# LVDS_IFC_DAC.net
KiCad netlist of a schematic drawn in Altium Designer
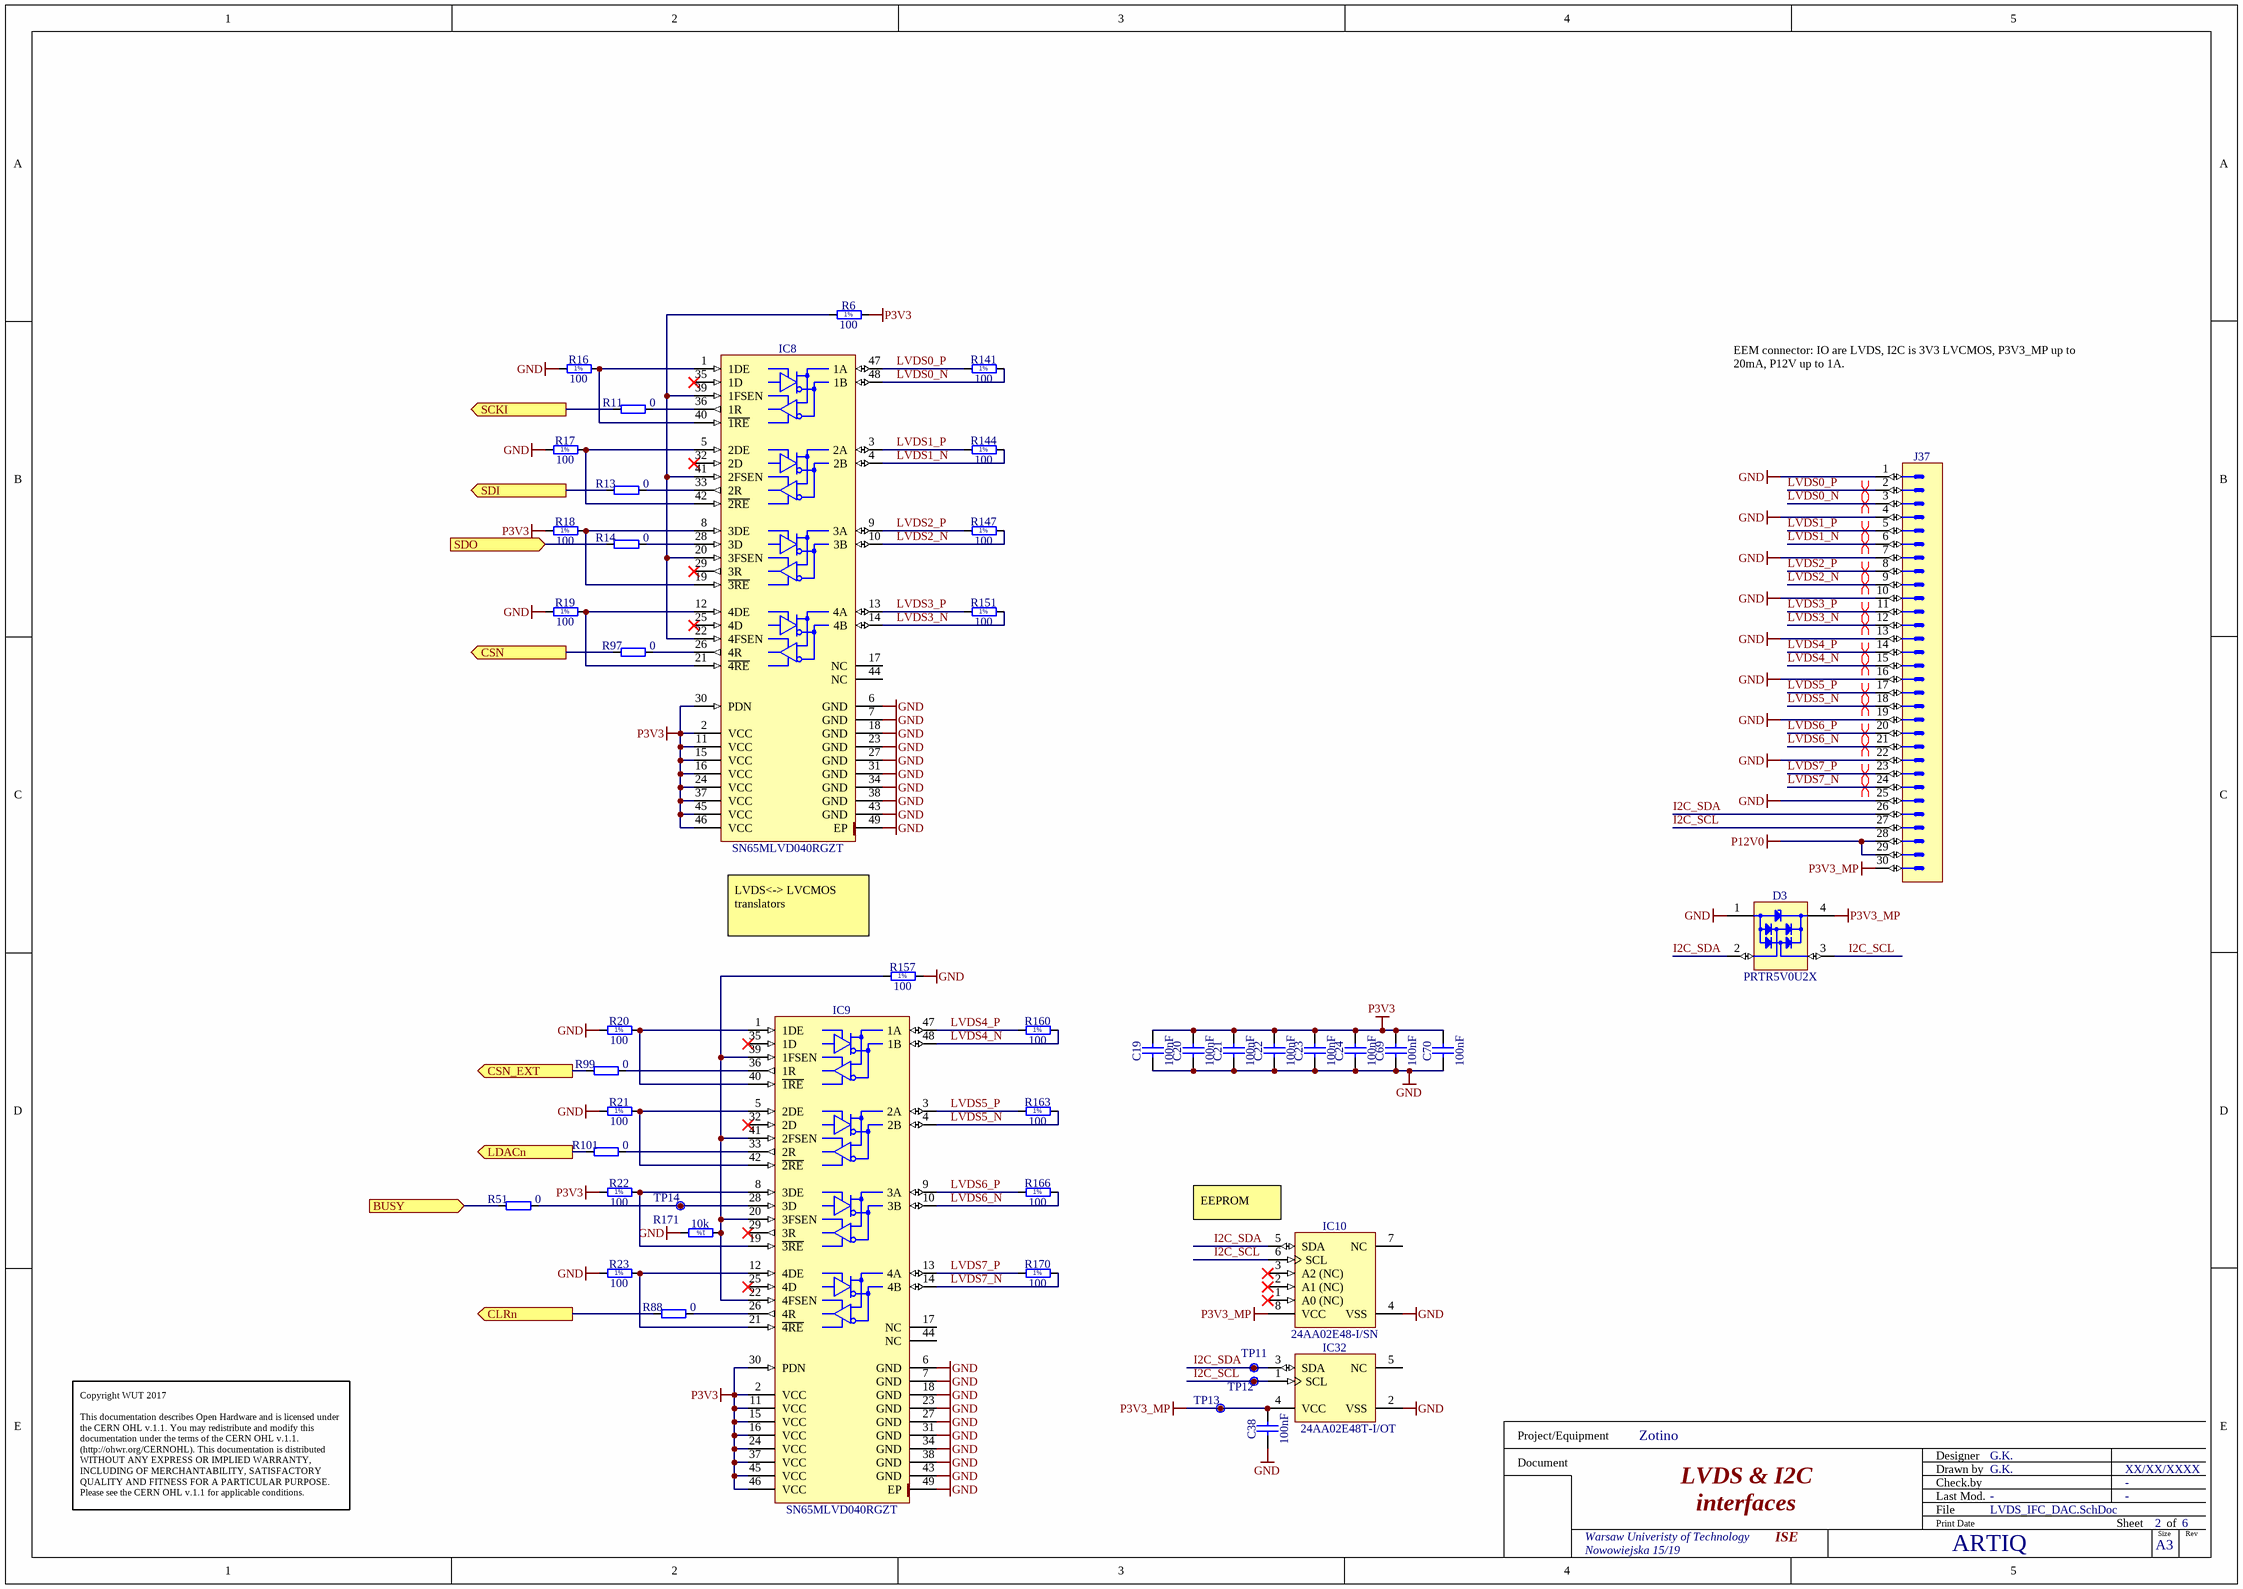
[diagram p0: LVDS_IFC_DAC.SchDoc]

(export (version "E")
  (design (tool "Eeschema 10.0.6"))
  (components
    (comp (ref "C19")
      (value "100nF")
      (footprint "CAPC1005X55N")
      (description "Non-polarised capacitor")
      (fields
        (field (name "PART NUMBER") "CC0402_100NF_16V_10%_X5R")
        (field (name "VOLTAGE") "16V")
        (field (name "AUTHOR") "CERN DEM JLC")
      )
      (libsource (lib "Capacitors") (part "Capacitor - non polarized"))
    )
    (comp (ref "C20")
      (value "100nF")
      (footprint "CAPC1005X55N")
      (description "Non-polarised capacitor")
      (fields
        (field (name "PART NUMBER") "CC0402_100NF_16V_10%_X5R")
        (field (name "VOLTAGE") "16V")
        (field (name "AUTHOR") "CERN DEM JLC")
      )
      (libsource (lib "Capacitors") (part "Capacitor - non polarized"))
    )
    (comp (ref "C21")
      (value "100nF")
      (footprint "CAPC1005X55N")
      (description "Non-polarised capacitor")
      (fields
        (field (name "PART NUMBER") "CC0402_100NF_16V_10%_X5R")
        (field (name "VOLTAGE") "16V")
        (field (name "AUTHOR") "CERN DEM JLC")
      )
      (libsource (lib "Capacitors") (part "Capacitor - non polarized"))
    )
    (comp (ref "C22")
      (value "100nF")
      (footprint "CAPC1005X55N")
      (description "Non-polarised capacitor")
      (fields
        (field (name "PART NUMBER") "CC0402_100NF_16V_10%_X5R")
        (field (name "VOLTAGE") "16V")
        (field (name "AUTHOR") "CERN DEM JLC")
      )
      (libsource (lib "Capacitors") (part "Capacitor - non polarized"))
    )
    (comp (ref "C23")
      (value "100nF")
      (footprint "CAPC1005X55N")
      (description "Non-polarised capacitor")
      (fields
        (field (name "PART NUMBER") "CC0402_100NF_16V_10%_X5R")
        (field (name "VOLTAGE") "16V")
        (field (name "AUTHOR") "CERN DEM JLC")
      )
      (libsource (lib "Capacitors") (part "Capacitor - non polarized"))
    )
    (comp (ref "C24")
      (value "100nF")
      (footprint "CAPC1005X55N")
      (description "Non-polarised capacitor")
      (fields
        (field (name "PART NUMBER") "CC0402_100NF_16V_10%_X5R")
        (field (name "VOLTAGE") "16V")
        (field (name "AUTHOR") "CERN DEM JLC")
      )
      (libsource (lib "Capacitors") (part "Capacitor - non polarized"))
    )
    (comp (ref "C38")
      (value "100nF")
      (footprint "CAPC1005X55N")
      (description "Non-polarised capacitor")
      (fields
        (field (name "PART NUMBER") "CC0402_100NF_16V_10%_X5R")
        (field (name "VOLTAGE") "16V")
        (field (name "AUTHOR") "CERN DEM JLC")
      )
      (libsource (lib "Capacitors") (part "Capacitor - non polarized"))
    )
    (comp (ref "C69")
      (value "100nF")
      (footprint "CAPC1005X55N")
      (description "Non-polarised capacitor")
      (fields
        (field (name "PART NUMBER") "CC0402_100NF_16V_10%_X5R")
        (field (name "VOLTAGE") "16V")
        (field (name "AUTHOR") "CERN DEM JLC")
      )
      (libsource (lib "Capacitors") (part "Capacitor - non polarized"))
    )
    (comp (ref "C70")
      (value "100nF")
      (footprint "CAPC1005X55N")
      (description "Non-polarised capacitor")
      (fields
        (field (name "PART NUMBER") "CC0402_100NF_16V_10%_X5R")
        (field (name "VOLTAGE") "16V")
        (field (name "AUTHOR") "CERN DEM JLC")
      )
      (libsource (lib "Capacitors") (part "Capacitor - non polarized"))
    )
    (comp (ref "D3")
      (value "PRTR5V0U2X")
      (footprint "SOT190P230X110-4N")
      (description "Ultra Low Capacitance Double Rail-to-Rail ESD Protection Diode")
      (fields
        (field (name "VOLTAGE") "5.5V")
        (field (name "MANUFACTURER") "NXP SEMICONDUCTORS")
        (field (name "AUTHOR") "CERN DEM JLC")
      )
      (libsource (lib "ICs And Semiconductors") (part "PRTR5V0U2X"))
    )
    (comp (ref "IC8")
      (value "SN65MLVD040RGZT")
      (footprint "QFN50P700X700X100-49N-S420")
      (description "4-Channel Half-Duplex M-LVDS Line Transceiver")
      (fields (field (name "MANUFACTURER") "TEXAS INSTRUMENTS") (field (name "AUTHOR") "CERN DEM JLC"))
      (libsource (lib "ICs And Semiconductors") (part "SN65MLVD040"))
    )
    (comp (ref "IC9")
      (value "SN65MLVD040RGZT")
      (footprint "QFN50P700X700X100-49N-S420")
      (description "4-Channel Half-Duplex M-LVDS Line Transceiver")
      (fields (field (name "MANUFACTURER") "TEXAS INSTRUMENTS") (field (name "AUTHOR") "CERN DEM JLC"))
      (libsource (lib "ICs And Semiconductors") (part "SN65MLVD040"))
    )
    (comp (ref "IC10")
      (value "24AA02E48-I/SN")
      (footprint "SOIC127P600X175-8N")
      (description "1.7V-5.5V, 2K I2C™ Serial EEPROMs with EUI-48™ Node Identity")
      (fields (field (name "MANUFACTURER") "MICROCHIP TECHNOLOGY") (field (name "AUTHOR") "CERN DEM MR"))
      (libsource (lib "ICS-logic") (part "MEM_24AA02E48-I/SN"))
    )
    (comp (ref "IC32")
      (value "24AA02E48T-I/OT")
      (footprint "SOT95P280X145-5N")
      (description "1.7V-5.5V, 2K I2C Serial EEPROM With EUI-48 Node Identity")
      (fields (field (name "MANUFACTURER") "MICROCHIP TECHNOLOGY") (field (name "AUTHOR") "CERN DEM MR"))
      (libsource (lib "ICs And Semiconductors") (part "24AA02E48T-I/OT"))
    )
    (comp (ref "J37")
      (value "~")
      (footprint "3M_N2530-6002RB")
      (description "Connector 30 Male")
      (fields
        (field (name "PART NUMBER") "3M_N2530-6002RB")
        (field (name "MANUFACTURER") "3M")
        (field (name "AUTHOR") "CERN DEM JLC")
      )
      (libsource (lib "Connectors") (part "Connector 30 Male"))
    )
    (comp (ref "R6")
      (value "100")
      (footprint "RESC1005X40N")
      (description "Resistor - 1%")
      (fields
        (field (name "PART NUMBER") "R0402_100R_1%_0.1W_100PPM")
        (field (name "POWER") "0.1W")
        (field (name "AUTHOR") "CERN DEM JLC")
      )
      (libsource (lib "Resistors") (part "Resistor - 1%"))
    )
    (comp (ref "R11")
      (value "0")
      (footprint "RESC1005X40N")
      (description "Resistor")
      (fields
        (field (name "PART NUMBER") "R0402_0R_JUMPER")
        (field (name "MANUFACTURER") "GENERIC")
        (field (name "AUTHOR") "CERN DEM JLC")
      )
      (libsource (lib "Resistors") (part "Resistor"))
    )
    (comp (ref "R13")
      (value "0")
      (footprint "RESC1005X40N")
      (description "Resistor")
      (fields
        (field (name "PART NUMBER") "R0402_0R_JUMPER")
        (field (name "MANUFACTURER") "GENERIC")
        (field (name "AUTHOR") "CERN DEM JLC")
      )
      (libsource (lib "Resistors") (part "Resistor"))
    )
    (comp (ref "R14")
      (value "0")
      (footprint "RESC1005X40N")
      (description "Resistor")
      (fields
        (field (name "PART NUMBER") "R0402_0R_JUMPER")
        (field (name "MANUFACTURER") "GENERIC")
        (field (name "AUTHOR") "CERN DEM JLC")
      )
      (libsource (lib "Resistors") (part "Resistor"))
    )
    (comp (ref "R16")
      (value "100")
      (footprint "RESC1005X40N")
      (description "Resistor - 1%")
      (fields
        (field (name "PART NUMBER") "R0402_100R_1%_0.1W_100PPM")
        (field (name "POWER") "0.1W")
        (field (name "AUTHOR") "CERN DEM JLC")
      )
      (libsource (lib "Resistors") (part "Resistor - 1%"))
    )
    (comp (ref "R17")
      (value "100")
      (footprint "RESC1005X40N")
      (description "Resistor - 1%")
      (fields
        (field (name "PART NUMBER") "R0402_100R_1%_0.1W_100PPM")
        (field (name "POWER") "0.1W")
        (field (name "AUTHOR") "CERN DEM JLC")
      )
      (libsource (lib "Resistors") (part "Resistor - 1%"))
    )
    (comp (ref "R18")
      (value "100")
      (footprint "RESC1005X40N")
      (description "Resistor - 1%")
      (fields
        (field (name "PART NUMBER") "R0402_100R_1%_0.1W_100PPM")
        (field (name "POWER") "0.1W")
        (field (name "AUTHOR") "CERN DEM JLC")
      )
      (libsource (lib "Resistors") (part "Resistor - 1%"))
    )
    (comp (ref "R19")
      (value "100")
      (footprint "RESC1005X40N")
      (description "Resistor - 1%")
      (fields
        (field (name "PART NUMBER") "R0402_100R_1%_0.1W_100PPM")
        (field (name "POWER") "0.1W")
        (field (name "AUTHOR") "CERN DEM JLC")
      )
      (libsource (lib "Resistors") (part "Resistor - 1%"))
    )
    (comp (ref "R20")
      (value "100")
      (footprint "RESC1005X40N")
      (description "Resistor - 1%")
      (fields
        (field (name "PART NUMBER") "R0402_100R_1%_0.1W_100PPM")
        (field (name "POWER") "0.1W")
        (field (name "AUTHOR") "CERN DEM JLC")
      )
      (libsource (lib "Resistors") (part "Resistor - 1%"))
    )
    (comp (ref "R21")
      (value "100")
      (footprint "RESC1005X40N")
      (description "Resistor - 1%")
      (fields
        (field (name "PART NUMBER") "R0402_100R_1%_0.1W_100PPM")
        (field (name "POWER") "0.1W")
        (field (name "AUTHOR") "CERN DEM JLC")
      )
      (libsource (lib "Resistors") (part "Resistor - 1%"))
    )
    (comp (ref "R22")
      (value "100")
      (footprint "RESC1005X40N")
      (description "Resistor - 1%")
      (fields
        (field (name "PART NUMBER") "R0402_100R_1%_0.1W_100PPM")
        (field (name "POWER") "0.1W")
        (field (name "AUTHOR") "CERN DEM JLC")
      )
      (libsource (lib "Resistors") (part "Resistor - 1%"))
    )
    (comp (ref "R23")
      (value "100")
      (footprint "RESC1005X40N")
      (description "Resistor - 1%")
      (fields
        (field (name "PART NUMBER") "R0402_100R_1%_0.1W_100PPM")
        (field (name "POWER") "0.1W")
        (field (name "AUTHOR") "CERN DEM JLC")
      )
      (libsource (lib "Resistors") (part "Resistor - 1%"))
    )
    (comp (ref "R51")
      (value "0")
      (footprint "RESC1005X40N")
      (description "Resistor")
      (fields
        (field (name "PART NUMBER") "R0402_0R_JUMPER")
        (field (name "MANUFACTURER") "GENERIC")
        (field (name "AUTHOR") "CERN DEM JLC")
      )
      (libsource (lib "Resistors") (part "Resistor"))
    )
    (comp (ref "R88")
      (value "0")
      (footprint "RESC1005X40N")
      (description "Resistor")
      (fields
        (field (name "PART NUMBER") "R0402_0R_JUMPER")
        (field (name "MANUFACTURER") "GENERIC")
        (field (name "AUTHOR") "CERN DEM JLC")
      )
      (libsource (lib "Resistors") (part "Resistor"))
    )
    (comp (ref "R97")
      (value "0")
      (footprint "RESC1005X40N")
      (description "Resistor")
      (fields
        (field (name "PART NUMBER") "R0402_0R_JUMPER")
        (field (name "MANUFACTURER") "GENERIC")
        (field (name "AUTHOR") "CERN DEM JLC")
      )
      (libsource (lib "Resistors") (part "Resistor"))
    )
    (comp (ref "R99")
      (value "0")
      (footprint "RESC1005X40N")
      (description "Resistor")
      (fields
        (field (name "PART NUMBER") "R0402_0R_JUMPER")
        (field (name "MANUFACTURER") "GENERIC")
        (field (name "AUTHOR") "CERN DEM JLC")
      )
      (libsource (lib "Resistors") (part "Resistor"))
    )
    (comp (ref "R101")
      (value "0")
      (footprint "RESC1005X40N")
      (description "Resistor")
      (fields
        (field (name "PART NUMBER") "R0402_0R_JUMPER")
        (field (name "MANUFACTURER") "GENERIC")
        (field (name "AUTHOR") "CERN DEM JLC")
      )
      (libsource (lib "Resistors") (part "Resistor"))
    )
    (comp (ref "R141")
      (value "100")
      (footprint "RESC1005X40N")
      (description "Resistor - 1%")
      (fields
        (field (name "PART NUMBER") "R0402_100R_1%_0.1W_100PPM")
        (field (name "POWER") "0.1W")
        (field (name "AUTHOR") "CERN DEM JLC")
      )
      (libsource (lib "Resistors") (part "Resistor - 1%"))
    )
    (comp (ref "R144")
      (value "100")
      (footprint "RESC1005X40N")
      (description "Resistor - 1%")
      (fields
        (field (name "PART NUMBER") "R0402_100R_1%_0.1W_100PPM")
        (field (name "POWER") "0.1W")
        (field (name "AUTHOR") "CERN DEM JLC")
      )
      (libsource (lib "Resistors") (part "Resistor - 1%"))
    )
    (comp (ref "R147")
      (value "100")
      (footprint "RESC1005X40N")
      (description "Resistor - 1%")
      (fields
        (field (name "PART NUMBER") "R0402_100R_1%_0.1W_100PPM")
        (field (name "POWER") "0.1W")
        (field (name "AUTHOR") "CERN DEM JLC")
      )
      (libsource (lib "Resistors") (part "Resistor - 1%"))
    )
    (comp (ref "R151")
      (value "100")
      (footprint "RESC1005X40N")
      (description "Resistor - 1%")
      (fields
        (field (name "PART NUMBER") "R0402_100R_1%_0.1W_100PPM")
        (field (name "POWER") "0.1W")
        (field (name "AUTHOR") "CERN DEM JLC")
      )
      (libsource (lib "Resistors") (part "Resistor - 1%"))
    )
    (comp (ref "R157")
      (value "100")
      (footprint "RESC1005X40N")
      (description "Resistor - 1%")
      (fields
        (field (name "PART NUMBER") "R0402_100R_1%_0.1W_100PPM")
        (field (name "POWER") "0.1W")
        (field (name "AUTHOR") "CERN DEM JLC")
      )
      (libsource (lib "Resistors") (part "Resistor - 1%"))
    )
    (comp (ref "R160")
      (value "100")
      (footprint "RESC1005X40N")
      (description "Resistor - 1%")
      (fields
        (field (name "PART NUMBER") "R0402_100R_1%_0.1W_100PPM")
        (field (name "POWER") "0.1W")
        (field (name "AUTHOR") "CERN DEM JLC")
      )
      (libsource (lib "Resistors") (part "Resistor - 1%"))
    )
    (comp (ref "R163")
      (value "100")
      (footprint "RESC1005X40N")
      (description "Resistor - 1%")
      (fields
        (field (name "PART NUMBER") "R0402_100R_1%_0.1W_100PPM")
        (field (name "POWER") "0.1W")
        (field (name "AUTHOR") "CERN DEM JLC")
      )
      (libsource (lib "Resistors") (part "Resistor - 1%"))
    )
    (comp (ref "R166")
      (value "100")
      (footprint "RESC1005X40N")
      (description "Resistor - 1%")
      (fields
        (field (name "PART NUMBER") "R0402_100R_1%_0.1W_100PPM")
        (field (name "POWER") "0.1W")
        (field (name "AUTHOR") "CERN DEM JLC")
      )
      (libsource (lib "Resistors") (part "Resistor - 1%"))
    )
    (comp (ref "R170")
      (value "100")
      (footprint "RESC1005X40N")
      (description "Resistor - 1%")
      (fields
        (field (name "PART NUMBER") "R0402_100R_1%_0.1W_100PPM")
        (field (name "POWER") "0.1W")
        (field (name "AUTHOR") "CERN DEM JLC")
      )
      (libsource (lib "Resistors") (part "Resistor - 1%"))
    )
    (comp (ref "R171")
      (value "10k")
      (footprint "RESC1005X40N")
      (description "Resistor - 1%")
      (fields
        (field (name "PART NUMBER") "R0402_10K_1%_0.0625W_100PPM")
        (field (name "POWER") "0.0625W")
        (field (name "AUTHOR") "CERN DEM JLC")
      )
      (libsource (lib "Resistors") (part "Resistor - 1%"))
    )
    (comp (ref "TP11")
      (value "Test Point")
      (footprint "TPS127")
      (fields (field (name "PART NUMBER") "SMD_PAD_1.27X1.27MM") (field (name "AUTHOR") "CERN DEM JLC"))
      (libsource (lib "Eletro-mechanical") (part "Test Point"))
    )
    (comp (ref "TP12")
      (value "Test Point")
      (footprint "TPS127")
      (fields (field (name "PART NUMBER") "SMD_PAD_1.27X1.27MM") (field (name "AUTHOR") "CERN DEM JLC"))
      (libsource (lib "Eletro-mechanical") (part "Test Point"))
    )
    (comp (ref "TP13")
      (value "Test Point")
      (footprint "TPS127")
      (fields (field (name "PART NUMBER") "SMD_PAD_1.27X1.27MM") (field (name "AUTHOR") "CERN DEM JLC"))
      (libsource (lib "Eletro-mechanical") (part "Test Point"))
    )
    (comp (ref "TP14")
      (value "Test Point")
      (footprint "TPS127")
      (fields (field (name "PART NUMBER") "SMD_PAD_1.27X1.27MM") (field (name "AUTHOR") "CERN DEM JLC"))
      (libsource (lib "Eletro-mechanical") (part "Test Point"))
    )
  )
  (nets
    (net (code "1") (name "/BUSY") (class "Default")
      (node (ref "R51") (pin "1") (pinfunction "1_1") (pintype "passive"))
    )
    (net (code "2") (name "/CLRn") (class "Default")
      (node (ref "R88") (pin "1") (pinfunction "1_1") (pintype "passive"))
    )
    (net (code "3") (name "/CSN") (class "Default")
      (node (ref "R97") (pin "1") (pinfunction "1_1") (pintype "passive"))
    )
    (net (code "4") (name "/CSN_EXT") (class "Default")
      (node (ref "R99") (pin "1") (pinfunction "1_1") (pintype "passive"))
    )
    (net (code "5") (name "/I2C_SCL") (class "Default")
      (node (ref "D3") (pin "3") (pinfunction "I/O2_3") (pintype "bidirectional"))
      (node (ref "IC10") (pin "6") (pinfunction "SCL_6") (pintype "input"))
      (node (ref "IC32") (pin "1") (pinfunction "SCL_1") (pintype "input"))
      (node (ref "J37") (pin "27") (pinfunction "27_27") (pintype "bidirectional"))
      (node (ref "TP12") (pin "1") (pinfunction "1_1") (pintype "bidirectional"))
    )
    (net (code "6") (name "/I2C_SDA") (class "Default")
      (node (ref "D3") (pin "2") (pinfunction "I/O1_2") (pintype "bidirectional"))
      (node (ref "IC10") (pin "5") (pinfunction "SDA_5") (pintype "bidirectional"))
      (node (ref "IC32") (pin "3") (pinfunction "SDA_3") (pintype "bidirectional"))
      (node (ref "J37") (pin "26") (pinfunction "26_26") (pintype "bidirectional"))
      (node (ref "TP11") (pin "1") (pinfunction "1_1") (pintype "bidirectional"))
    )
    (net (code "7") (name "/LDACn") (class "Default")
      (node (ref "R101") (pin "1") (pinfunction "1_1") (pintype "passive"))
    )
    (net (code "8") (name "/LVDS0_N") (class "Default")
      (node (ref "IC8") (pin "48") (pinfunction "1B_48") (pintype "bidirectional"))
      (node (ref "J37") (pin "3") (pinfunction "3_3") (pintype "bidirectional"))
      (node (ref "R141") (pin "2") (pinfunction "2_2") (pintype "passive"))
    )
    (net (code "9") (name "/LVDS0_P") (class "Default")
      (node (ref "IC8") (pin "47") (pinfunction "1A_47") (pintype "bidirectional"))
      (node (ref "J37") (pin "2") (pinfunction "2_2") (pintype "bidirectional"))
      (node (ref "R141") (pin "1") (pinfunction "1_1") (pintype "passive"))
    )
    (net (code "10") (name "/LVDS1_N") (class "Default")
      (node (ref "IC8") (pin "4") (pinfunction "2B_4") (pintype "bidirectional"))
      (node (ref "J37") (pin "6") (pinfunction "6_6") (pintype "bidirectional"))
      (node (ref "R144") (pin "2") (pinfunction "2_2") (pintype "passive"))
    )
    (net (code "11") (name "/LVDS1_P") (class "Default")
      (node (ref "IC8") (pin "3") (pinfunction "2A_3") (pintype "bidirectional"))
      (node (ref "J37") (pin "5") (pinfunction "5_5") (pintype "bidirectional"))
      (node (ref "R144") (pin "1") (pinfunction "1_1") (pintype "passive"))
    )
    (net (code "12") (name "/LVDS2_N") (class "Default")
      (node (ref "IC8") (pin "10") (pinfunction "3B_10") (pintype "bidirectional"))
      (node (ref "J37") (pin "9") (pinfunction "9_9") (pintype "bidirectional"))
      (node (ref "R147") (pin "2") (pinfunction "2_2") (pintype "passive"))
    )
    (net (code "13") (name "/LVDS2_P") (class "Default")
      (node (ref "IC8") (pin "9") (pinfunction "3A_9") (pintype "bidirectional"))
      (node (ref "J37") (pin "8") (pinfunction "8_8") (pintype "bidirectional"))
      (node (ref "R147") (pin "1") (pinfunction "1_1") (pintype "passive"))
    )
    (net (code "14") (name "/LVDS3_N") (class "Default")
      (node (ref "IC8") (pin "14") (pinfunction "4B_14") (pintype "bidirectional"))
      (node (ref "J37") (pin "12") (pinfunction "12_12") (pintype "bidirectional"))
      (node (ref "R151") (pin "2") (pinfunction "2_2") (pintype "passive"))
    )
    (net (code "15") (name "/LVDS3_P") (class "Default")
      (node (ref "IC8") (pin "13") (pinfunction "4A_13") (pintype "bidirectional"))
      (node (ref "J37") (pin "11") (pinfunction "11_11") (pintype "bidirectional"))
      (node (ref "R151") (pin "1") (pinfunction "1_1") (pintype "passive"))
    )
    (net (code "16") (name "/LVDS4_N") (class "Default")
      (node (ref "IC9") (pin "48") (pinfunction "1B_48") (pintype "bidirectional"))
      (node (ref "J37") (pin "15") (pinfunction "15_15") (pintype "bidirectional"))
      (node (ref "R160") (pin "2") (pinfunction "2_2") (pintype "passive"))
    )
    (net (code "17") (name "/LVDS4_P") (class "Default")
      (node (ref "IC9") (pin "47") (pinfunction "1A_47") (pintype "bidirectional"))
      (node (ref "J37") (pin "14") (pinfunction "14_14") (pintype "bidirectional"))
      (node (ref "R160") (pin "1") (pinfunction "1_1") (pintype "passive"))
    )
    (net (code "18") (name "/LVDS5_N") (class "Default")
      (node (ref "IC9") (pin "4") (pinfunction "2B_4") (pintype "bidirectional"))
      (node (ref "J37") (pin "18") (pinfunction "18_18") (pintype "bidirectional"))
      (node (ref "R163") (pin "2") (pinfunction "2_2") (pintype "passive"))
    )
    (net (code "19") (name "/LVDS5_P") (class "Default")
      (node (ref "IC9") (pin "3") (pinfunction "2A_3") (pintype "bidirectional"))
      (node (ref "J37") (pin "17") (pinfunction "17_17") (pintype "bidirectional"))
      (node (ref "R163") (pin "1") (pinfunction "1_1") (pintype "passive"))
    )
    (net (code "20") (name "/LVDS6_N") (class "Default")
      (node (ref "IC9") (pin "10") (pinfunction "3B_10") (pintype "bidirectional"))
      (node (ref "J37") (pin "21") (pinfunction "21_21") (pintype "bidirectional"))
      (node (ref "R166") (pin "2") (pinfunction "2_2") (pintype "passive"))
    )
    (net (code "21") (name "/LVDS6_P") (class "Default")
      (node (ref "IC9") (pin "9") (pinfunction "3A_9") (pintype "bidirectional"))
      (node (ref "J37") (pin "20") (pinfunction "20_20") (pintype "bidirectional"))
      (node (ref "R166") (pin "1") (pinfunction "1_1") (pintype "passive"))
    )
    (net (code "22") (name "/LVDS7_N") (class "Default")
      (node (ref "IC9") (pin "14") (pinfunction "4B_14") (pintype "bidirectional"))
      (node (ref "J37") (pin "24") (pinfunction "24_24") (pintype "bidirectional"))
      (node (ref "R170") (pin "2") (pinfunction "2_2") (pintype "passive"))
    )
    (net (code "23") (name "/LVDS7_P") (class "Default")
      (node (ref "IC9") (pin "13") (pinfunction "4A_13") (pintype "bidirectional"))
      (node (ref "J37") (pin "23") (pinfunction "23_23") (pintype "bidirectional"))
      (node (ref "R170") (pin "1") (pinfunction "1_1") (pintype "passive"))
    )
    (net (code "24") (name "/SCKI") (class "Default")
      (node (ref "R11") (pin "1") (pinfunction "1_1") (pintype "passive"))
    )
    (net (code "25") (name "/SDI") (class "Default")
      (node (ref "R13") (pin "1") (pinfunction "1_1") (pintype "passive"))
    )
    (net (code "26") (name "/SDO") (class "Default")
      (node (ref "R14") (pin "1") (pinfunction "1_1") (pintype "passive"))
    )
    (net (code "27") (name "GND") (class "Default")
      (node (ref "C19") (pin "1") (pinfunction "1_1") (pintype "passive"))
      (node (ref "C20") (pin "1") (pinfunction "1_1") (pintype "passive"))
      (node (ref "C21") (pin "1") (pinfunction "1_1") (pintype "passive"))
      (node (ref "C22") (pin "1") (pinfunction "1_1") (pintype "passive"))
      (node (ref "C23") (pin "1") (pinfunction "1_1") (pintype "passive"))
      (node (ref "C24") (pin "1") (pinfunction "1_1") (pintype "passive"))
      (node (ref "C38") (pin "1") (pinfunction "1_1") (pintype "passive"))
      (node (ref "C69") (pin "1") (pinfunction "1_1") (pintype "passive"))
      (node (ref "C70") (pin "1") (pinfunction "1_1") (pintype "passive"))
      (node (ref "D3") (pin "1") (pinfunction "GND_1") (pintype "power_in"))
      (node (ref "IC10") (pin "4") (pinfunction "VSS_4") (pintype "power_in"))
      (node (ref "IC32") (pin "2") (pinfunction "VSS_2") (pintype "power_in"))
      (node (ref "IC8") (pin "18") (pinfunction "GND_18") (pintype "power_in"))
      (node (ref "IC8") (pin "23") (pinfunction "GND_23") (pintype "power_in"))
      (node (ref "IC8") (pin "27") (pinfunction "GND_27") (pintype "power_in"))
      (node (ref "IC8") (pin "31") (pinfunction "GND_31") (pintype "power_in"))
      (node (ref "IC8") (pin "34") (pinfunction "GND_34") (pintype "power_in"))
      (node (ref "IC8") (pin "38") (pinfunction "GND_38") (pintype "power_in"))
      (node (ref "IC8") (pin "43") (pinfunction "GND_43") (pintype "power_in"))
      (node (ref "IC8") (pin "49") (pinfunction "EP_49") (pintype "power_in"))
      (node (ref "IC8") (pin "6") (pinfunction "GND_6") (pintype "power_in"))
      (node (ref "IC8") (pin "7") (pinfunction "GND_7") (pintype "power_in"))
      (node (ref "IC9") (pin "18") (pinfunction "GND_18") (pintype "power_in"))
      (node (ref "IC9") (pin "23") (pinfunction "GND_23") (pintype "power_in"))
      (node (ref "IC9") (pin "27") (pinfunction "GND_27") (pintype "power_in"))
      (node (ref "IC9") (pin "31") (pinfunction "GND_31") (pintype "power_in"))
      (node (ref "IC9") (pin "34") (pinfunction "GND_34") (pintype "power_in"))
      (node (ref "IC9") (pin "38") (pinfunction "GND_38") (pintype "power_in"))
      (node (ref "IC9") (pin "43") (pinfunction "GND_43") (pintype "power_in"))
      (node (ref "IC9") (pin "49") (pinfunction "EP_49") (pintype "power_in"))
      (node (ref "IC9") (pin "6") (pinfunction "GND_6") (pintype "power_in"))
      (node (ref "IC9") (pin "7") (pinfunction "GND_7") (pintype "power_in"))
      (node (ref "J37") (pin "1") (pinfunction "1_1") (pintype "bidirectional"))
      (node (ref "J37") (pin "10") (pinfunction "10_10") (pintype "bidirectional"))
      (node (ref "J37") (pin "13") (pinfunction "13_13") (pintype "bidirectional"))
      (node (ref "J37") (pin "16") (pinfunction "16_16") (pintype "bidirectional"))
      (node (ref "J37") (pin "19") (pinfunction "19_19") (pintype "bidirectional"))
      (node (ref "J37") (pin "22") (pinfunction "22_22") (pintype "bidirectional"))
      (node (ref "J37") (pin "25") (pinfunction "25_25") (pintype "bidirectional"))
      (node (ref "J37") (pin "4") (pinfunction "4_4") (pintype "bidirectional"))
      (node (ref "J37") (pin "7") (pinfunction "7_7") (pintype "bidirectional"))
      (node (ref "R157") (pin "2") (pinfunction "2_2") (pintype "passive"))
      (node (ref "R16") (pin "1") (pinfunction "1_1") (pintype "passive"))
      (node (ref "R17") (pin "1") (pinfunction "1_1") (pintype "passive"))
      (node (ref "R171") (pin "2") (pinfunction "2_2") (pintype "passive"))
      (node (ref "R19") (pin "1") (pinfunction "1_1") (pintype "passive"))
      (node (ref "R20") (pin "1") (pinfunction "1_1") (pintype "passive"))
      (node (ref "R21") (pin "1") (pinfunction "1_1") (pintype "passive"))
      (node (ref "R23") (pin "1") (pinfunction "1_1") (pintype "passive"))
    )
    (net (code "28") (name "Net-(IC8-1DE)") (class "Default")
      (node (ref "IC8") (pin "1") (pinfunction "1DE_1") (pintype "input"))
      (node (ref "IC8") (pin "40") (pinfunction "~{1RE}_40") (pintype "input"))
      (node (ref "R16") (pin "2") (pinfunction "2_2") (pintype "passive"))
    )
    (net (code "29") (name "Net-(IC8-1FSEN)") (class "Default")
      (node (ref "IC8") (pin "20") (pinfunction "3FSEN_20") (pintype "input"))
      (node (ref "IC8") (pin "22") (pinfunction "4FSEN_22") (pintype "input"))
      (node (ref "IC8") (pin "39") (pinfunction "1FSEN_39") (pintype "input"))
      (node (ref "IC8") (pin "41") (pinfunction "2FSEN_41") (pintype "input"))
      (node (ref "R6") (pin "1") (pinfunction "1_1") (pintype "passive"))
    )
    (net (code "30") (name "Net-(IC8-1R)") (class "Default")
      (node (ref "IC8") (pin "36") (pinfunction "1R_36") (pintype "output"))
      (node (ref "R11") (pin "2") (pinfunction "2_2") (pintype "passive"))
    )
    (net (code "31") (name "Net-(IC8-2DE)") (class "Default")
      (node (ref "IC8") (pin "42") (pinfunction "~{2RE}_42") (pintype "input"))
      (node (ref "IC8") (pin "5") (pinfunction "2DE_5") (pintype "input"))
      (node (ref "R17") (pin "2") (pinfunction "2_2") (pintype "passive"))
    )
    (net (code "32") (name "Net-(IC8-2R)") (class "Default")
      (node (ref "IC8") (pin "33") (pinfunction "2R_33") (pintype "output"))
      (node (ref "R13") (pin "2") (pinfunction "2_2") (pintype "passive"))
    )
    (net (code "33") (name "Net-(IC8-3D)") (class "Default")
      (node (ref "IC8") (pin "28") (pinfunction "3D_28") (pintype "input"))
      (node (ref "R14") (pin "2") (pinfunction "2_2") (pintype "passive"))
    )
    (net (code "34") (name "Net-(IC8-3DE)") (class "Default")
      (node (ref "IC8") (pin "19") (pinfunction "~{3RE}_19") (pintype "input"))
      (node (ref "IC8") (pin "8") (pinfunction "3DE_8") (pintype "input"))
      (node (ref "R18") (pin "2") (pinfunction "2_2") (pintype "passive"))
    )
    (net (code "35") (name "Net-(IC8-4DE)") (class "Default")
      (node (ref "IC8") (pin "12") (pinfunction "4DE_12") (pintype "input"))
      (node (ref "IC8") (pin "21") (pinfunction "~{4RE}_21") (pintype "input"))
      (node (ref "R19") (pin "2") (pinfunction "2_2") (pintype "passive"))
    )
    (net (code "36") (name "Net-(IC8-4R)") (class "Default")
      (node (ref "IC8") (pin "26") (pinfunction "4R_26") (pintype "output"))
      (node (ref "R97") (pin "2") (pinfunction "2_2") (pintype "passive"))
    )
    (net (code "37") (name "Net-(IC9-1DE)") (class "Default")
      (node (ref "IC9") (pin "1") (pinfunction "1DE_1") (pintype "input"))
      (node (ref "IC9") (pin "40") (pinfunction "~{1RE}_40") (pintype "input"))
      (node (ref "R20") (pin "2") (pinfunction "2_2") (pintype "passive"))
    )
    (net (code "38") (name "Net-(IC9-1FSEN)") (class "Default")
      (node (ref "IC9") (pin "20") (pinfunction "3FSEN_20") (pintype "input"))
      (node (ref "IC9") (pin "22") (pinfunction "4FSEN_22") (pintype "input"))
      (node (ref "IC9") (pin "39") (pinfunction "1FSEN_39") (pintype "input"))
      (node (ref "IC9") (pin "41") (pinfunction "2FSEN_41") (pintype "input"))
      (node (ref "R157") (pin "1") (pinfunction "1_1") (pintype "passive"))
      (node (ref "R171") (pin "1") (pinfunction "1_1") (pintype "passive"))
    )
    (net (code "39") (name "Net-(IC9-1R)") (class "Default")
      (node (ref "IC9") (pin "36") (pinfunction "1R_36") (pintype "output"))
      (node (ref "R99") (pin "2") (pinfunction "2_2") (pintype "passive"))
    )
    (net (code "40") (name "Net-(IC9-2DE)") (class "Default")
      (node (ref "IC9") (pin "42") (pinfunction "~{2RE}_42") (pintype "input"))
      (node (ref "IC9") (pin "5") (pinfunction "2DE_5") (pintype "input"))
      (node (ref "R21") (pin "2") (pinfunction "2_2") (pintype "passive"))
    )
    (net (code "41") (name "Net-(IC9-2R)") (class "Default")
      (node (ref "IC9") (pin "33") (pinfunction "2R_33") (pintype "output"))
      (node (ref "R101") (pin "2") (pinfunction "2_2") (pintype "passive"))
    )
    (net (code "42") (name "Net-(IC9-3D)") (class "Default")
      (node (ref "IC9") (pin "28") (pinfunction "3D_28") (pintype "input"))
      (node (ref "R51") (pin "2") (pinfunction "2_2") (pintype "passive"))
      (node (ref "TP14") (pin "1") (pinfunction "1_1") (pintype "bidirectional"))
    )
    (net (code "43") (name "Net-(IC9-3DE)") (class "Default")
      (node (ref "IC9") (pin "19") (pinfunction "~{3RE}_19") (pintype "input"))
      (node (ref "IC9") (pin "8") (pinfunction "3DE_8") (pintype "input"))
      (node (ref "R22") (pin "2") (pinfunction "2_2") (pintype "passive"))
    )
    (net (code "44") (name "Net-(IC9-4DE)") (class "Default")
      (node (ref "IC9") (pin "12") (pinfunction "4DE_12") (pintype "input"))
      (node (ref "IC9") (pin "21") (pinfunction "~{4RE}_21") (pintype "input"))
      (node (ref "R23") (pin "2") (pinfunction "2_2") (pintype "passive"))
    )
    (net (code "45") (name "Net-(IC9-4R)") (class "Default")
      (node (ref "IC9") (pin "26") (pinfunction "4R_26") (pintype "output"))
      (node (ref "R88") (pin "2") (pinfunction "2_2") (pintype "passive"))
    )
    (net (code "46") (name "P3V3") (class "Default")
      (node (ref "C19") (pin "2") (pinfunction "2_2") (pintype "passive"))
      (node (ref "C20") (pin "2") (pinfunction "2_2") (pintype "passive"))
      (node (ref "C21") (pin "2") (pinfunction "2_2") (pintype "passive"))
      (node (ref "C22") (pin "2") (pinfunction "2_2") (pintype "passive"))
      (node (ref "C23") (pin "2") (pinfunction "2_2") (pintype "passive"))
      (node (ref "C24") (pin "2") (pinfunction "2_2") (pintype "passive"))
      (node (ref "C69") (pin "2") (pinfunction "2_2") (pintype "passive"))
      (node (ref "C70") (pin "2") (pinfunction "2_2") (pintype "passive"))
      (node (ref "IC8") (pin "11") (pinfunction "VCC_11") (pintype "power_in"))
      (node (ref "IC8") (pin "15") (pinfunction "VCC_15") (pintype "power_in"))
      (node (ref "IC8") (pin "16") (pinfunction "VCC_16") (pintype "power_in"))
      (node (ref "IC8") (pin "2") (pinfunction "VCC_2") (pintype "power_in"))
      (node (ref "IC8") (pin "24") (pinfunction "VCC_24") (pintype "power_in"))
      (node (ref "IC8") (pin "30") (pinfunction "PDN_30") (pintype "input"))
      (node (ref "IC8") (pin "37") (pinfunction "VCC_37") (pintype "power_in"))
      (node (ref "IC8") (pin "45") (pinfunction "VCC_45") (pintype "power_in"))
      (node (ref "IC8") (pin "46") (pinfunction "VCC_46") (pintype "power_in"))
      (node (ref "IC9") (pin "11") (pinfunction "VCC_11") (pintype "power_in"))
      (node (ref "IC9") (pin "15") (pinfunction "VCC_15") (pintype "power_in"))
      (node (ref "IC9") (pin "16") (pinfunction "VCC_16") (pintype "power_in"))
      (node (ref "IC9") (pin "2") (pinfunction "VCC_2") (pintype "power_in"))
      (node (ref "IC9") (pin "24") (pinfunction "VCC_24") (pintype "power_in"))
      (node (ref "IC9") (pin "30") (pinfunction "PDN_30") (pintype "input"))
      (node (ref "IC9") (pin "37") (pinfunction "VCC_37") (pintype "power_in"))
      (node (ref "IC9") (pin "45") (pinfunction "VCC_45") (pintype "power_in"))
      (node (ref "IC9") (pin "46") (pinfunction "VCC_46") (pintype "power_in"))
      (node (ref "R18") (pin "1") (pinfunction "1_1") (pintype "passive"))
      (node (ref "R22") (pin "1") (pinfunction "1_1") (pintype "passive"))
      (node (ref "R6") (pin "2") (pinfunction "2_2") (pintype "passive"))
    )
    (net (code "47") (name "P3V3_MP") (class "Default")
      (node (ref "C38") (pin "2") (pinfunction "2_2") (pintype "passive"))
      (node (ref "D3") (pin "4") (pinfunction "VCC_4") (pintype "power_in"))
      (node (ref "IC10") (pin "8") (pinfunction "VCC_8") (pintype "power_in"))
      (node (ref "IC32") (pin "4") (pinfunction "VCC_4") (pintype "power_in"))
      (node (ref "J37") (pin "30") (pinfunction "30_30") (pintype "bidirectional"))
      (node (ref "TP13") (pin "1") (pinfunction "1_1") (pintype "bidirectional"))
    )
    (net (code "48") (name "P12V0") (class "Default")
      (node (ref "J37") (pin "28") (pinfunction "28_28") (pintype "bidirectional"))
      (node (ref "J37") (pin "29") (pinfunction "29_29") (pintype "bidirectional"))
    )
    (net (code "49") (name "unconnected-(IC8-1D-Pad35)") (class "Default")
      (node (ref "IC8") (pin "35") (pinfunction "1D_35") (pintype "input+no_connect"))
    )
    (net (code "50") (name "unconnected-(IC8-2D-Pad32)") (class "Default")
      (node (ref "IC8") (pin "32") (pinfunction "2D_32") (pintype "input+no_connect"))
    )
    (net (code "51") (name "unconnected-(IC8-3R-Pad29)") (class "Default")
      (node (ref "IC8") (pin "29") (pinfunction "3R_29") (pintype "output+no_connect"))
    )
    (net (code "52") (name "unconnected-(IC8-4D-Pad25)") (class "Default")
      (node (ref "IC8") (pin "25") (pinfunction "4D_25") (pintype "input+no_connect"))
    )
    (net (code "53") (name "unconnected-(IC8-NC-Pad17)") (class "Default")
      (node (ref "IC8") (pin "17") (pinfunction "NC_17") (pintype "passive"))
    )
    (net (code "54") (name "unconnected-(IC8-NC-Pad44)") (class "Default")
      (node (ref "IC8") (pin "44") (pinfunction "NC_44") (pintype "passive"))
    )
    (net (code "55") (name "unconnected-(IC9-1D-Pad35)") (class "Default")
      (node (ref "IC9") (pin "35") (pinfunction "1D_35") (pintype "input+no_connect"))
    )
    (net (code "56") (name "unconnected-(IC9-2D-Pad32)") (class "Default")
      (node (ref "IC9") (pin "32") (pinfunction "2D_32") (pintype "input+no_connect"))
    )
    (net (code "57") (name "unconnected-(IC9-3R-Pad29)") (class "Default")
      (node (ref "IC9") (pin "29") (pinfunction "3R_29") (pintype "output+no_connect"))
    )
    (net (code "58") (name "unconnected-(IC9-4D-Pad25)") (class "Default")
      (node (ref "IC9") (pin "25") (pinfunction "4D_25") (pintype "input+no_connect"))
    )
    (net (code "59") (name "unconnected-(IC9-NC-Pad17)") (class "Default")
      (node (ref "IC9") (pin "17") (pinfunction "NC_17") (pintype "passive"))
    )
    (net (code "60") (name "unconnected-(IC9-NC-Pad44)") (class "Default")
      (node (ref "IC9") (pin "44") (pinfunction "NC_44") (pintype "passive"))
    )
    (net (code "61") (name "unconnected-(IC10-A0_(NC)-Pad1)") (class "Default")
      (node (ref "IC10") (pin "1") (pinfunction "A0_(NC)_1") (pintype "input+no_connect"))
    )
    (net (code "62") (name "unconnected-(IC10-A1_(NC)-Pad2)") (class "Default")
      (node (ref "IC10") (pin "2") (pinfunction "A1_(NC)_2") (pintype "input+no_connect"))
    )
    (net (code "63") (name "unconnected-(IC10-A2_(NC)-Pad3)") (class "Default")
      (node (ref "IC10") (pin "3") (pinfunction "A2_(NC)_3") (pintype "input+no_connect"))
    )
    (net (code "64") (name "unconnected-(IC10-NC-Pad7)") (class "Default")
      (node (ref "IC10") (pin "7") (pinfunction "NC_7") (pintype "passive"))
    )
    (net (code "65") (name "unconnected-(IC32-NC-Pad5)") (class "Default")
      (node (ref "IC32") (pin "5") (pinfunction "NC_5") (pintype "passive"))
    )
  )
)
